# LedDriver.net
KiCad netlist of a schematic drawn in EAGLE
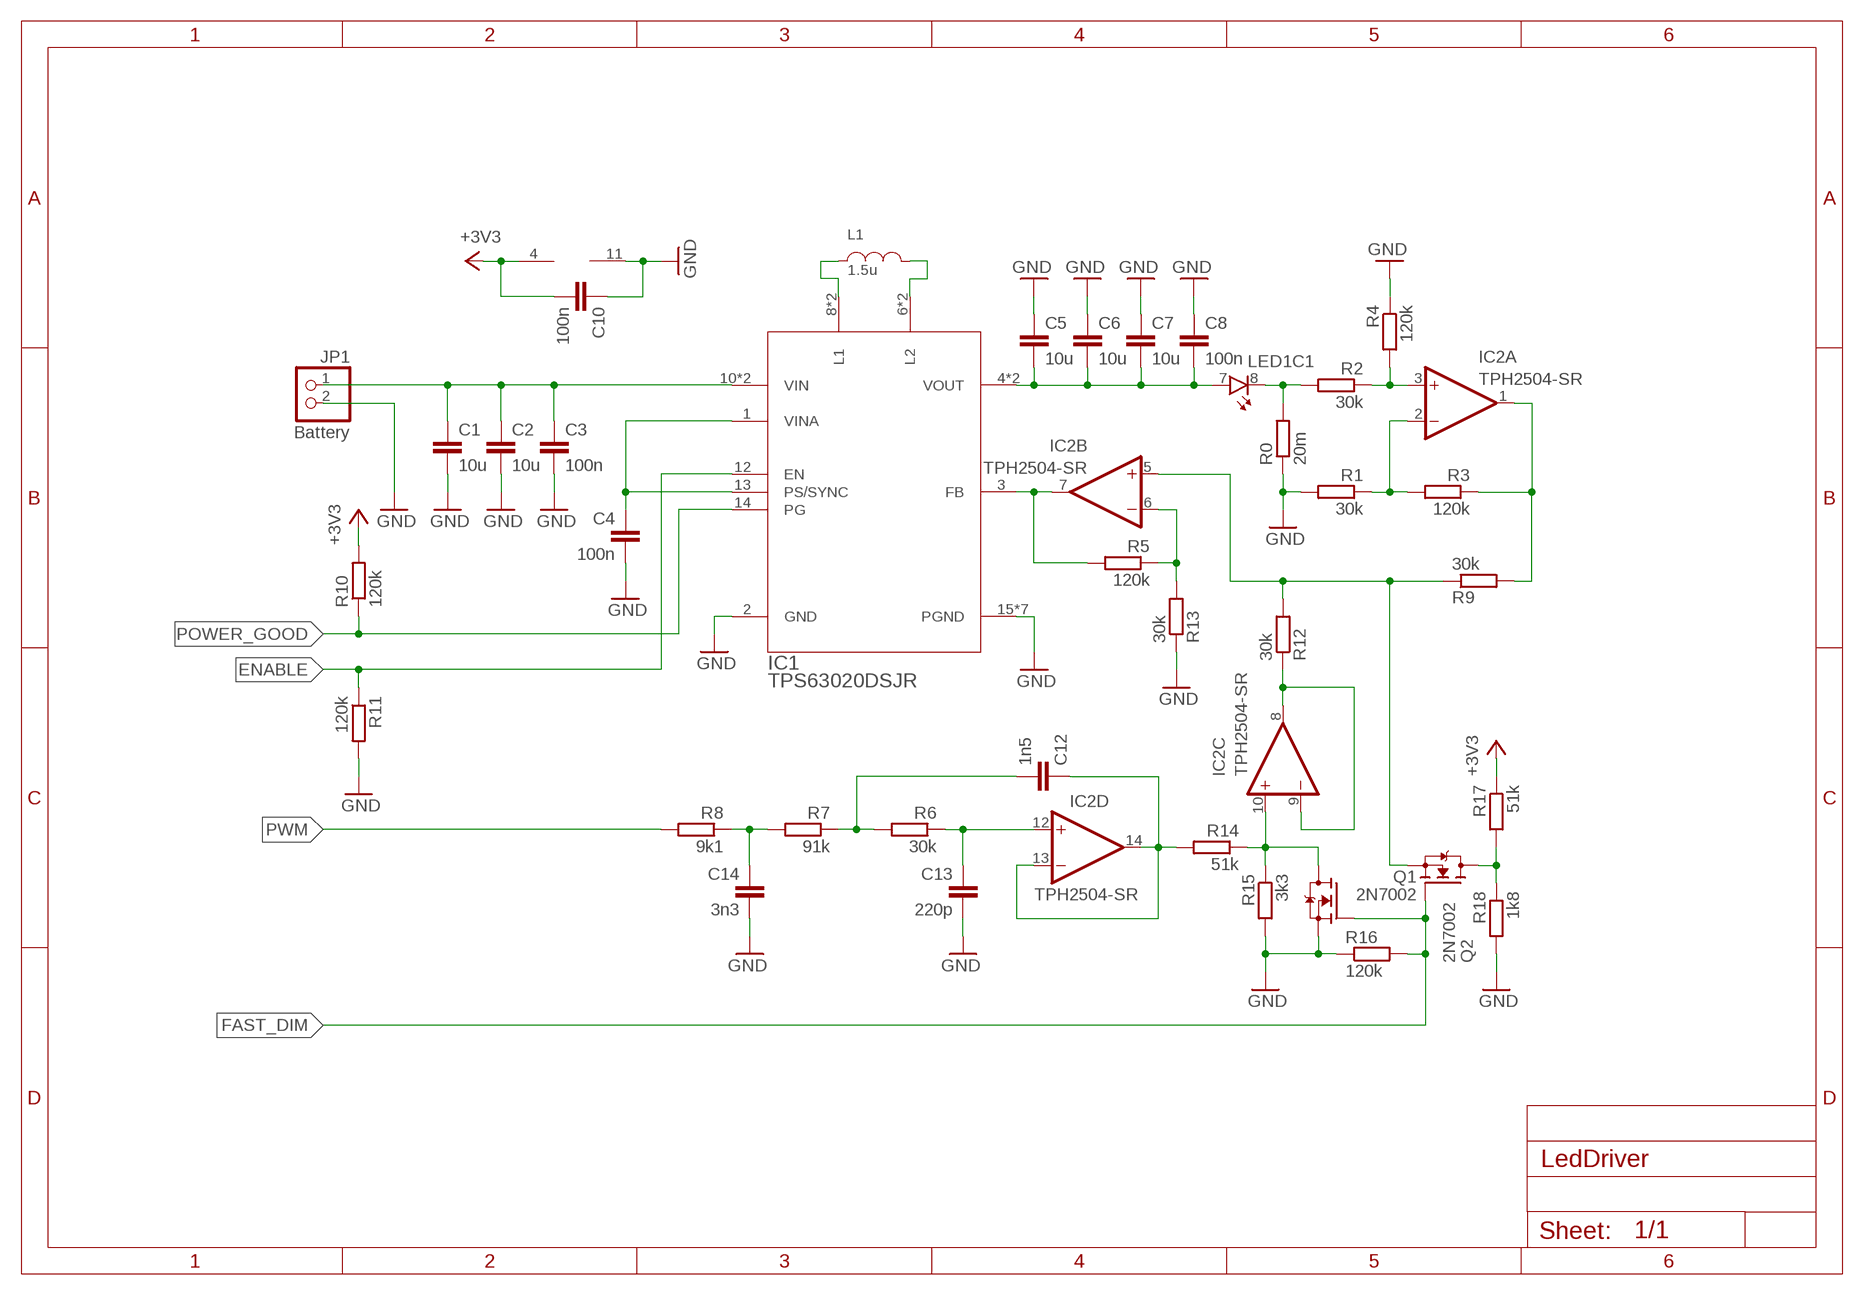
[diagram p0: schematic, sheet 1]

(export (version "E")
  (design (tool "Eeschema 10.0.6"))
  (components
    (comp (ref "C1")
      (value "10u")
      (footprint "eagle-import:C0603")
      (libsource (lib "eagle-import") (part "C-EUC0603"))
    )
    (comp (ref "C2")
      (value "10u")
      (footprint "eagle-import:C0603")
      (libsource (lib "eagle-import") (part "C-EUC0603"))
    )
    (comp (ref "C3")
      (value "100n")
      (footprint "eagle-import:C0603")
      (libsource (lib "eagle-import") (part "C-EUC0603"))
    )
    (comp (ref "C4")
      (value "100n")
      (footprint "eagle-import:C0603")
      (libsource (lib "eagle-import") (part "C-EUC0603"))
    )
    (comp (ref "C5")
      (value "10u")
      (footprint "eagle-import:C0603")
      (libsource (lib "eagle-import") (part "C-EUC0603"))
    )
    (comp (ref "C6")
      (value "10u")
      (footprint "eagle-import:C0603")
      (libsource (lib "eagle-import") (part "C-EUC0603"))
    )
    (comp (ref "C7")
      (value "10u")
      (footprint "eagle-import:C0603")
      (libsource (lib "eagle-import") (part "C-EUC0603"))
    )
    (comp (ref "C8")
      (value "100n")
      (footprint "eagle-import:C0603")
      (libsource (lib "eagle-import") (part "C-EUC0603"))
    )
    (comp (ref "C10")
      (value "100n")
      (footprint "eagle-import:C0603")
      (libsource (lib "eagle-import") (part "C-EUC0603"))
    )
    (comp (ref "C12")
      (value "1n5")
      (footprint "eagle-import:C0603")
      (libsource (lib "eagle-import") (part "C-EUC0603"))
    )
    (comp (ref "C13")
      (value "220p")
      (footprint "eagle-import:C0603")
      (libsource (lib "eagle-import") (part "C-EUC0603"))
    )
    (comp (ref "C14")
      (value "3n3")
      (footprint "eagle-import:C0603")
      (libsource (lib "eagle-import") (part "C-EUC0603"))
    )
    (comp (ref "IC1")
      (value "TPS63020DSJR")
      (footprint "eagle-import:DSJ14_2P85X1P58")
      (fields
        (field (name "GENERIC_PART_NUMBER") "TPS63020")
        (field (name "MANUFACTURER") "Texas Instruments")
      )
      (libsource (lib "eagle-import") (part "TPS63020DSJR"))
    )
    (comp (ref "IC2")
      (value "TPH2504-SR")
      (footprint "eagle-import:SO14")
      (fields (field (name "LCSC") "C115918"))
      (libsource (lib "eagle-import") (part "MCP604SL"))
    )
    (comp (ref "JP1")
      (value "Battery")
      (footprint "eagle-import:1X02")
      (libsource (lib "eagle-import") (part "PINHD-1X2"))
    )
    (comp (ref "L1")
      (value "1.5u")
      (footprint "eagle-import:5X5MM")
      (libsource (lib "eagle-import") (part "L5X5MM"))
    )
    (comp (ref "LED1")
      (value "ACULEDVHL-RGBY")
      (footprint "eagle-import:ACULEDVHL")
      (libsource (lib "eagle-import") (part "ACULEDVHL-RGBY"))
    )
    (comp (ref "Q1")
      (value "2N7002")
      (footprint "eagle-import:SOT23")
      (libsource (lib "eagle-import") (part "N-MOSFET-SOT23-GSD"))
    )
    (comp (ref "Q2")
      (value "2N7002")
      (footprint "eagle-import:SOT23")
      (libsource (lib "eagle-import") (part "N-MOSFET-SOT23-GSD"))
    )
    (comp (ref "R0")
      (value "20m")
      (footprint "eagle-import:R0805")
      (libsource (lib "eagle-import") (part "R-EU_R0805"))
    )
    (comp (ref "R1")
      (value "30k")
      (footprint "eagle-import:R0603")
      (libsource (lib "eagle-import") (part "R-EU_R0603"))
    )
    (comp (ref "R2")
      (value "30k")
      (footprint "eagle-import:R0603")
      (libsource (lib "eagle-import") (part "R-EU_R0603"))
    )
    (comp (ref "R3")
      (value "120k")
      (footprint "eagle-import:R0603")
      (libsource (lib "eagle-import") (part "R-EU_R0603"))
    )
    (comp (ref "R4")
      (value "120k")
      (footprint "eagle-import:R0603")
      (libsource (lib "eagle-import") (part "R-EU_R0603"))
    )
    (comp (ref "R5")
      (value "120k")
      (footprint "eagle-import:R0603")
      (libsource (lib "eagle-import") (part "R-EU_R0603"))
    )
    (comp (ref "R6")
      (value "30k")
      (footprint "eagle-import:R0603")
      (libsource (lib "eagle-import") (part "R-EU_R0603"))
    )
    (comp (ref "R7")
      (value "91k")
      (footprint "eagle-import:R0603")
      (libsource (lib "eagle-import") (part "R-EU_R0603"))
    )
    (comp (ref "R8")
      (value "9k1")
      (footprint "eagle-import:R0603")
      (libsource (lib "eagle-import") (part "R-EU_R0603"))
    )
    (comp (ref "R9")
      (value "30k")
      (footprint "eagle-import:R0603")
      (libsource (lib "eagle-import") (part "R-EU_R0603"))
    )
    (comp (ref "R10")
      (value "120k")
      (footprint "eagle-import:R0402")
      (libsource (lib "eagle-import") (part "R-EU_R0402"))
    )
    (comp (ref "R11")
      (value "120k")
      (footprint "eagle-import:R0402")
      (libsource (lib "eagle-import") (part "R-EU_R0402"))
    )
    (comp (ref "R12")
      (value "30k")
      (footprint "eagle-import:R0603")
      (libsource (lib "eagle-import") (part "R-EU_R0603"))
    )
    (comp (ref "R13")
      (value "30k")
      (footprint "eagle-import:R0603")
      (libsource (lib "eagle-import") (part "R-EU_R0603"))
    )
    (comp (ref "R14")
      (value "51k")
      (footprint "eagle-import:R0603")
      (libsource (lib "eagle-import") (part "R-EU_R0603"))
    )
    (comp (ref "R15")
      (value "3k3")
      (footprint "eagle-import:R0603")
      (libsource (lib "eagle-import") (part "R-EU_R0603"))
    )
    (comp (ref "R16")
      (value "120k")
      (footprint "eagle-import:R0402")
      (libsource (lib "eagle-import") (part "R-EU_R0402"))
    )
    (comp (ref "R17")
      (value "51k")
      (footprint "eagle-import:R0603")
      (libsource (lib "eagle-import") (part "R-EU_R0603"))
    )
    (comp (ref "R18")
      (value "1k8")
      (footprint "eagle-import:R0603")
      (libsource (lib "eagle-import") (part "R-EU_R0603"))
    )
  )
  (nets
    (net (code "1") (name "+3V3") (class "Default")
      (node (ref "C10") (pin "2") (pinfunction "2_2") (pintype "passive"))
      (node (ref "IC2") (pin "4") (pinfunction "V+_4") (pintype "power_in"))
      (node (ref "R10") (pin "2") (pinfunction "2_2") (pintype "passive"))
      (node (ref "R17") (pin "1") (pinfunction "1_1") (pintype "passive"))
    )
    (net (code "2") (name "ENABLE") (class "Default")
      (node (ref "IC1") (pin "12") (pinfunction "EN_12") (pintype "input"))
      (node (ref "R11") (pin "1") (pinfunction "1_1") (pintype "passive"))
    )
    (net (code "3") (name "FAST_DIM") (class "Default")
      (node (ref "Q1") (pin "1") (pinfunction "G_1") (pintype "passive"))
      (node (ref "Q2") (pin "1") (pinfunction "G_1") (pintype "passive"))
      (node (ref "R16") (pin "2") (pinfunction "2_2") (pintype "passive"))
    )
    (net (code "4") (name "GND") (class "Default")
      (node (ref "C1") (pin "2") (pinfunction "2_2") (pintype "passive"))
      (node (ref "C10") (pin "1") (pinfunction "1_1") (pintype "passive"))
      (node (ref "C13") (pin "2") (pinfunction "2_2") (pintype "passive"))
      (node (ref "C14") (pin "2") (pinfunction "2_2") (pintype "passive"))
      (node (ref "C2") (pin "2") (pinfunction "2_2") (pintype "passive"))
      (node (ref "C3") (pin "2") (pinfunction "2_2") (pintype "passive"))
      (node (ref "C4") (pin "2") (pinfunction "2_2") (pintype "passive"))
      (node (ref "C5") (pin "1") (pinfunction "1_1") (pintype "passive"))
      (node (ref "C6") (pin "1") (pinfunction "1_1") (pintype "passive"))
      (node (ref "C7") (pin "1") (pinfunction "1_1") (pintype "passive"))
      (node (ref "C8") (pin "1") (pinfunction "1_1") (pintype "passive"))
      (node (ref "IC1") (pin "15") (pinfunction "PGND_15") (pintype "passive"))
      (node (ref "IC1") (pin "2") (pinfunction "GND_2") (pintype "power_in"))
      (node (ref "IC1") (pin "V") (pinfunction "PGND_V") (pintype "passive"))
      (node (ref "IC1") (pin "V_1") (pinfunction "PGND_V_1") (pintype "passive"))
      (node (ref "IC1") (pin "V_2") (pinfunction "PGND_V_2") (pintype "passive"))
      (node (ref "IC1") (pin "V_3") (pinfunction "PGND_V_3") (pintype "passive"))
      (node (ref "IC1") (pin "V_4") (pinfunction "PGND_V_4") (pintype "passive"))
      (node (ref "IC1") (pin "V_5") (pinfunction "PGND_V_5") (pintype "passive"))
      (node (ref "IC2") (pin "11") (pinfunction "V-_11") (pintype "power_in"))
      (node (ref "JP1") (pin "2") (pinfunction "2_2") (pintype "passive"))
      (node (ref "Q1") (pin "2") (pinfunction "S_2") (pintype "passive"))
      (node (ref "R0") (pin "1") (pinfunction "1_1") (pintype "passive"))
      (node (ref "R1") (pin "2") (pinfunction "2_2") (pintype "passive"))
      (node (ref "R11") (pin "2") (pinfunction "2_2") (pintype "passive"))
      (node (ref "R13") (pin "1") (pinfunction "1_1") (pintype "passive"))
      (node (ref "R15") (pin "2") (pinfunction "2_2") (pintype "passive"))
      (node (ref "R16") (pin "1") (pinfunction "1_1") (pintype "passive"))
      (node (ref "R18") (pin "2") (pinfunction "2_2") (pintype "passive"))
      (node (ref "R4") (pin "1") (pinfunction "1_1") (pintype "passive"))
    )
    (net (code "5") (name "Net-(C1-Pad1)") (class "Default")
      (node (ref "C1") (pin "1") (pinfunction "1_1") (pintype "passive"))
      (node (ref "C2") (pin "1") (pinfunction "1_1") (pintype "passive"))
      (node (ref "C3") (pin "1") (pinfunction "1_1") (pintype "passive"))
      (node (ref "IC1") (pin "10") (pinfunction "VIN_10") (pintype "input"))
      (node (ref "IC1") (pin "11") (pinfunction "VIN_11") (pintype "input"))
      (node (ref "JP1") (pin "1") (pinfunction "1_1") (pintype "passive"))
    )
    (net (code "6") (name "Net-(C12-Pad2)") (class "Default")
      (node (ref "C12") (pin "2") (pinfunction "2_2") (pintype "passive"))
      (node (ref "R6") (pin "2") (pinfunction "2_2") (pintype "passive"))
      (node (ref "R7") (pin "1") (pinfunction "1_1") (pintype "passive"))
    )
    (net (code "7") (name "Net-(C14-Pad1)") (class "Default")
      (node (ref "C14") (pin "1") (pinfunction "1_1") (pintype "passive"))
      (node (ref "R7") (pin "2") (pinfunction "2_2") (pintype "passive"))
      (node (ref "R8") (pin "1") (pinfunction "1_1") (pintype "passive"))
    )
    (net (code "8") (name "Net-(IC1-FB)") (class "Default")
      (node (ref "IC1") (pin "3") (pinfunction "FB_3") (pintype "input"))
      (node (ref "IC2") (pin "7") (pinfunction "OUT_7") (pintype "output"))
      (node (ref "R5") (pin "2") (pinfunction "2_2") (pintype "passive"))
    )
    (net (code "9") (name "Net-(IC1-L1-Pad8)") (class "Default")
      (node (ref "IC1") (pin "8") (pinfunction "L1_8") (pintype "passive"))
      (node (ref "IC1") (pin "9") (pinfunction "L1_9") (pintype "passive"))
      (node (ref "L1") (pin "1") (pinfunction "1_1") (pintype "passive"))
    )
    (net (code "10") (name "Net-(IC1-L2-Pad6)") (class "Default")
      (node (ref "IC1") (pin "6") (pinfunction "L2_6") (pintype "passive"))
      (node (ref "IC1") (pin "7") (pinfunction "L2_7") (pintype "passive"))
      (node (ref "L1") (pin "2") (pinfunction "2_2") (pintype "passive"))
    )
    (net (code "11") (name "Net-(IC1-PS{slash}SYNC)") (class "Default")
      (node (ref "C4") (pin "1") (pinfunction "1_1") (pintype "passive"))
      (node (ref "IC1") (pin "1") (pinfunction "VINA_1") (pintype "input"))
      (node (ref "IC1") (pin "13") (pinfunction "PS/SYNC_13") (pintype "input"))
    )
    (net (code "12") (name "Net-(IC2A-+IN)") (class "Default")
      (node (ref "IC2") (pin "3") (pinfunction "+IN_3") (pintype "input"))
      (node (ref "R2") (pin "1") (pinfunction "1_1") (pintype "passive"))
      (node (ref "R4") (pin "2") (pinfunction "2_2") (pintype "passive"))
    )
    (net (code "13") (name "Net-(IC2A--IN)") (class "Default")
      (node (ref "IC2") (pin "2") (pinfunction "-IN_2") (pintype "input"))
      (node (ref "R1") (pin "1") (pinfunction "1_1") (pintype "passive"))
      (node (ref "R3") (pin "2") (pinfunction "2_2") (pintype "passive"))
    )
    (net (code "14") (name "Net-(IC2A-OUT)") (class "Default")
      (node (ref "IC2") (pin "1") (pinfunction "OUT_1") (pintype "output"))
      (node (ref "R3") (pin "1") (pinfunction "1_1") (pintype "passive"))
      (node (ref "R9") (pin "2") (pinfunction "2_2") (pintype "passive"))
    )
    (net (code "15") (name "Net-(IC2B-+IN)") (class "Default")
      (node (ref "IC2") (pin "5") (pinfunction "+IN_5") (pintype "input"))
      (node (ref "Q2") (pin "2") (pinfunction "S_2") (pintype "passive"))
      (node (ref "R12") (pin "2") (pinfunction "2_2") (pintype "passive"))
      (node (ref "R9") (pin "1") (pinfunction "1_1") (pintype "passive"))
    )
    (net (code "16") (name "Net-(IC2B--IN)") (class "Default")
      (node (ref "IC2") (pin "6") (pinfunction "-IN_6") (pintype "input"))
      (node (ref "R13") (pin "2") (pinfunction "2_2") (pintype "passive"))
      (node (ref "R5") (pin "1") (pinfunction "1_1") (pintype "passive"))
    )
    (net (code "17") (name "Net-(IC2C-+IN)") (class "Default")
      (node (ref "IC2") (pin "10") (pinfunction "+IN_10") (pintype "input"))
      (node (ref "Q1") (pin "3") (pinfunction "D_3") (pintype "passive"))
      (node (ref "R14") (pin "1") (pinfunction "1_1") (pintype "passive"))
      (node (ref "R15") (pin "1") (pinfunction "1_1") (pintype "passive"))
    )
    (net (code "18") (name "Net-(IC2C--IN)") (class "Default")
      (node (ref "IC2") (pin "8") (pinfunction "OUT_8") (pintype "output"))
      (node (ref "IC2") (pin "9") (pinfunction "-IN_9") (pintype "input"))
      (node (ref "R12") (pin "1") (pinfunction "1_1") (pintype "passive"))
    )
    (net (code "19") (name "Net-(IC2D-+IN)") (class "Default")
      (node (ref "C13") (pin "1") (pinfunction "1_1") (pintype "passive"))
      (node (ref "IC2") (pin "12") (pinfunction "+IN_12") (pintype "input"))
      (node (ref "R6") (pin "1") (pinfunction "1_1") (pintype "passive"))
    )
    (net (code "20") (name "Net-(IC2D--IN)") (class "Default")
      (node (ref "C12") (pin "1") (pinfunction "1_1") (pintype "passive"))
      (node (ref "IC2") (pin "13") (pinfunction "-IN_13") (pintype "input"))
      (node (ref "IC2") (pin "14") (pinfunction "OUT_14") (pintype "output"))
      (node (ref "R14") (pin "2") (pinfunction "2_2") (pintype "passive"))
    )
    (net (code "21") (name "Net-(LED1A-A)") (class "Default")
      (node (ref "C5") (pin "2") (pinfunction "2_2") (pintype "passive"))
      (node (ref "C6") (pin "2") (pinfunction "2_2") (pintype "passive"))
      (node (ref "C7") (pin "2") (pinfunction "2_2") (pintype "passive"))
      (node (ref "C8") (pin "2") (pinfunction "2_2") (pintype "passive"))
      (node (ref "IC1") (pin "4") (pinfunction "VOUT_4") (pintype "output"))
      (node (ref "IC1") (pin "5") (pinfunction "VOUT_5") (pintype "output"))
      (node (ref "LED1") (pin "7") (pinfunction "A_7") (pintype "passive"))
    )
    (net (code "22") (name "Net-(LED1A-C)") (class "Default")
      (node (ref "LED1") (pin "8") (pinfunction "C_8") (pintype "passive"))
      (node (ref "R0") (pin "2") (pinfunction "2_2") (pintype "passive"))
      (node (ref "R2") (pin "2") (pinfunction "2_2") (pintype "passive"))
    )
    (net (code "23") (name "Net-(Q2-D)") (class "Default")
      (node (ref "Q2") (pin "3") (pinfunction "D_3") (pintype "passive"))
      (node (ref "R17") (pin "2") (pinfunction "2_2") (pintype "passive"))
      (node (ref "R18") (pin "1") (pinfunction "1_1") (pintype "passive"))
    )
    (net (code "24") (name "POWER_GOOD") (class "Default")
      (node (ref "IC1") (pin "14") (pinfunction "PG_14") (pintype "open_collector"))
      (node (ref "R10") (pin "1") (pinfunction "1_1") (pintype "passive"))
    )
    (net (code "25") (name "PWM") (class "Default")
      (node (ref "R8") (pin "2") (pinfunction "2_2") (pintype "passive"))
    )
  )
)
